# PixiFlood.net
KiCad netlist of a schematic drawn in EAGLE
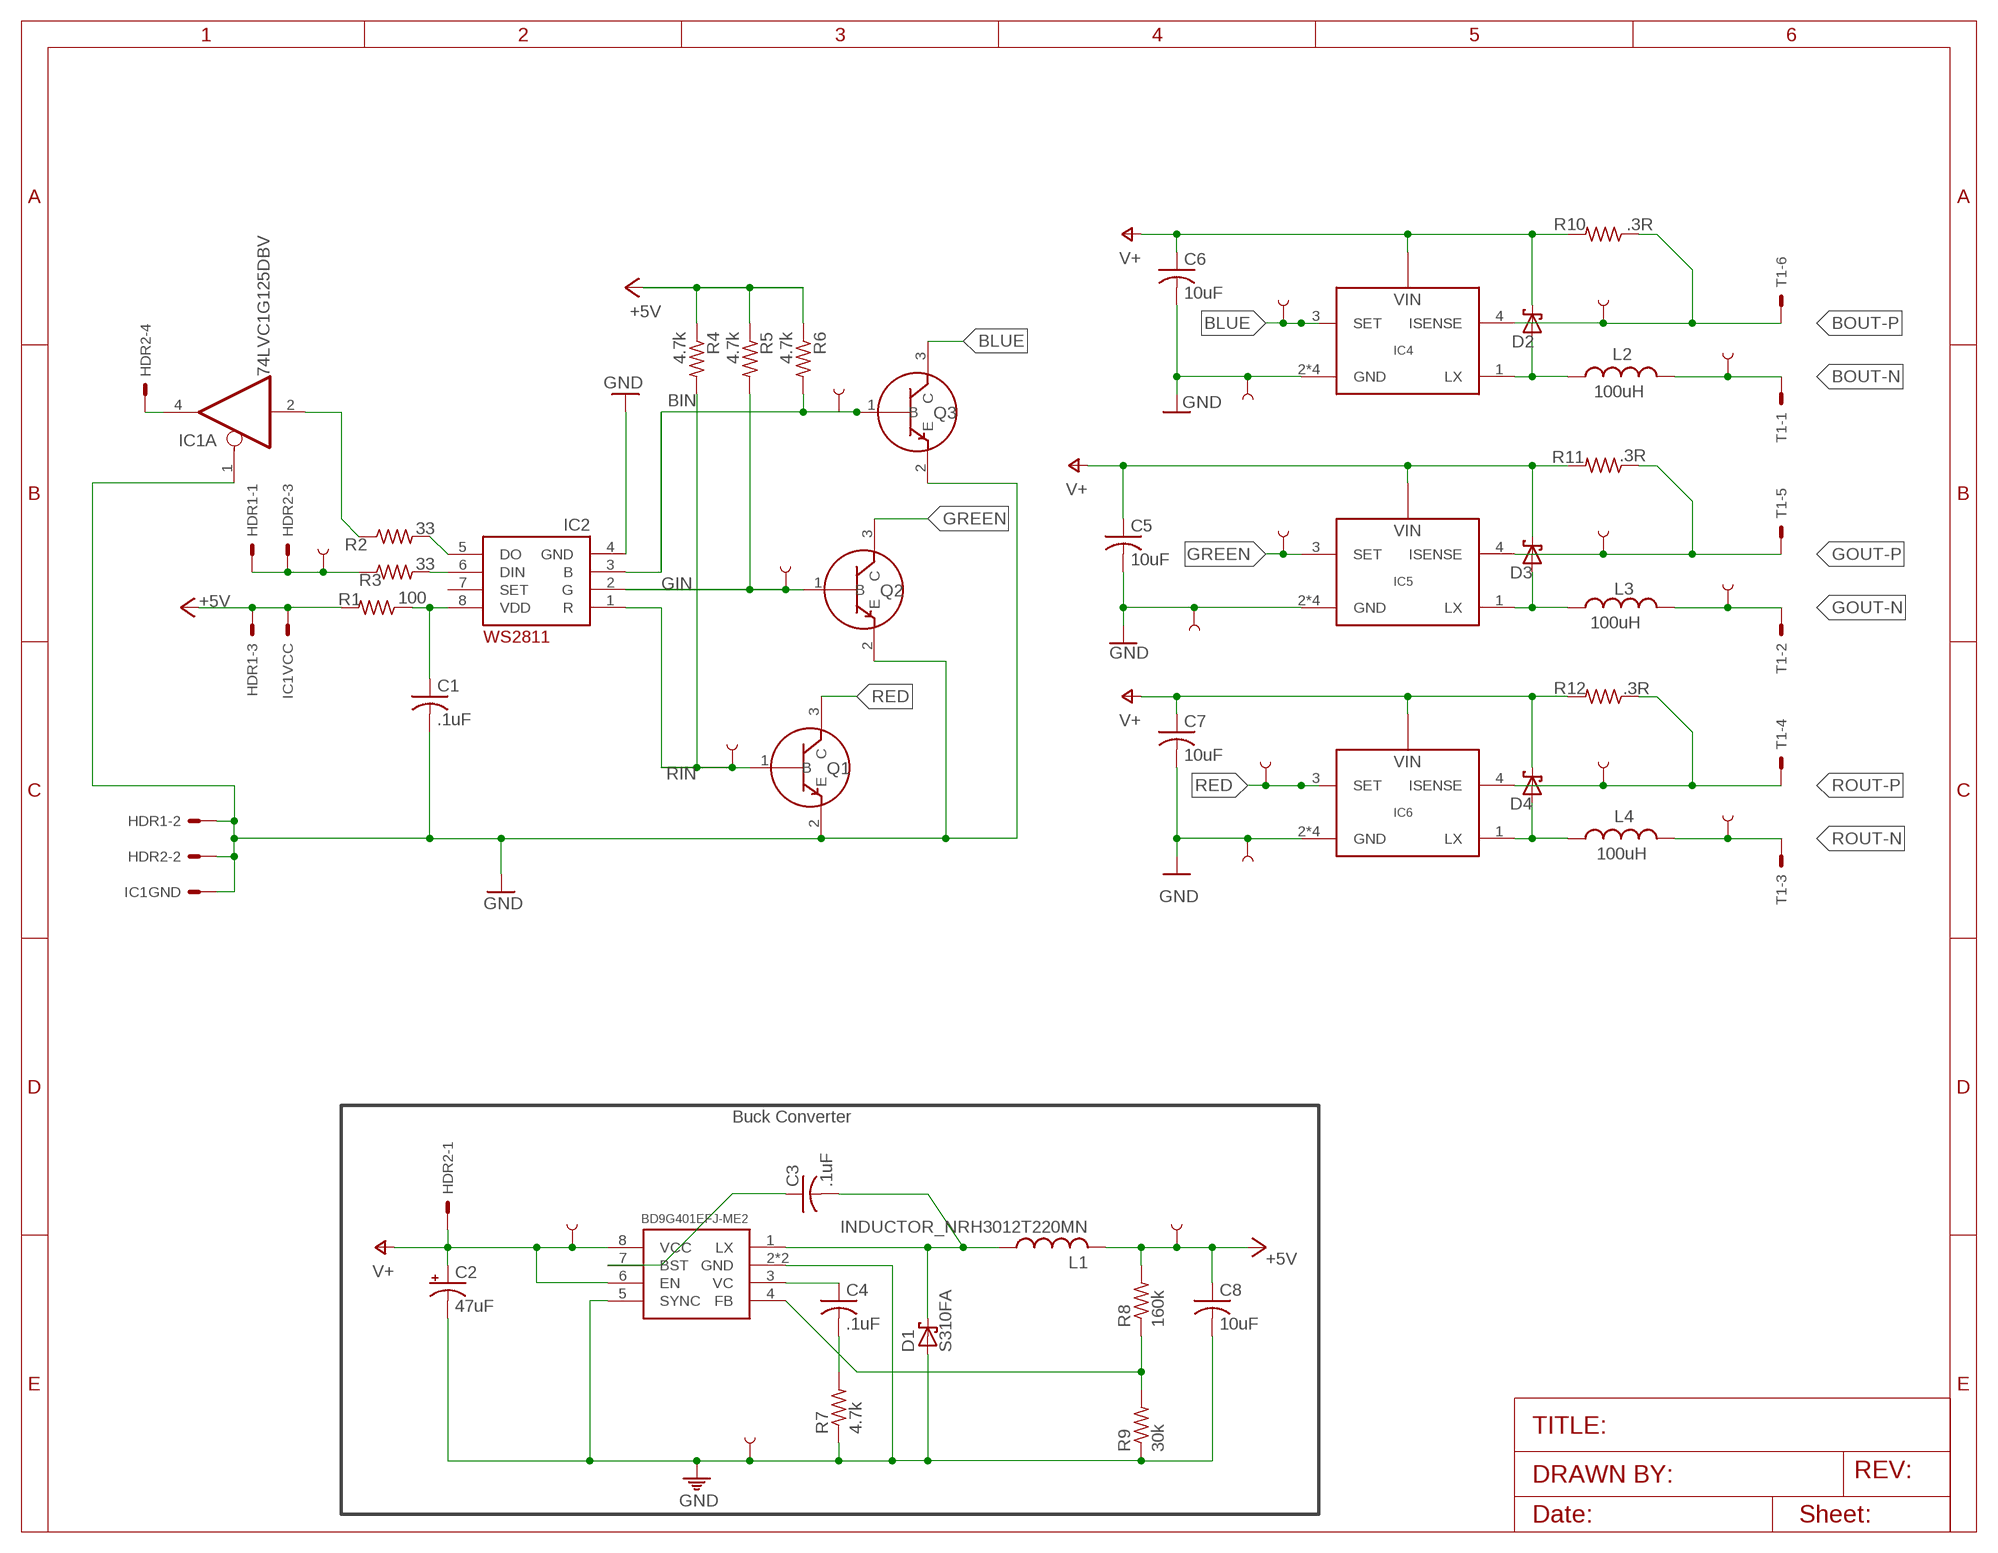
[diagram p0: schematic, sheet 1]

(export (version "E")
  (design (tool "Eeschema 10.0.6"))
  (components
    (comp (ref "C1")
      (value ".1uF")
      (footprint "eagle-import:C0805")
      (libsource (lib "eagle-import") (part "C-USC0805"))
    )
    (comp (ref "C2")
      (value "47uF")
      (footprint "eagle-import:UD-6,3X7,7_NICHICON")
      (libsource (lib "eagle-import") (part "CPOL-USUD-6,3X7,7"))
    )
    (comp (ref "C3")
      (value ".1uF")
      (footprint "eagle-import:C0805")
      (libsource (lib "eagle-import") (part "C-USC0805"))
    )
    (comp (ref "C4")
      (value ".1uF")
      (footprint "eagle-import:C0805")
      (libsource (lib "eagle-import") (part "C-USC0805"))
    )
    (comp (ref "C5")
      (value "10uF")
      (footprint "eagle-import:C1206")
      (libsource (lib "eagle-import") (part "C-USC1206"))
    )
    (comp (ref "C6")
      (value "10uF")
      (footprint "eagle-import:C1206")
      (libsource (lib "eagle-import") (part "C-USC1206"))
    )
    (comp (ref "C7")
      (value "10uF")
      (footprint "eagle-import:C1206")
      (libsource (lib "eagle-import") (part "C-USC1206"))
    )
    (comp (ref "C8")
      (value "10uF")
      (footprint "eagle-import:C1206")
      (libsource (lib "eagle-import") (part "C-USC1206"))
    )
    (comp (ref "D1")
      (value "S310FA")
      (footprint "eagle-import:SOD-123FL")
      (libsource (lib "eagle-import") (part "SCHOTTKY-DIODES310FA"))
    )
    (comp (ref "D2")
      (value "S310FA")
      (footprint "eagle-import:SOD-123FL")
      (libsource (lib "eagle-import") (part "SCHOTTKY-DIODES310FA"))
    )
    (comp (ref "D3")
      (value "S310FA")
      (footprint "eagle-import:SOD-123FL")
      (libsource (lib "eagle-import") (part "SCHOTTKY-DIODES310FA"))
    )
    (comp (ref "D4")
      (value "S310FA")
      (footprint "eagle-import:SOD-123FL")
      (libsource (lib "eagle-import") (part "SCHOTTKY-DIODES310FA"))
    )
    (comp (ref "HDR1")
      (value "M03FEMALE")
      (footprint "eagle-import:1X03_FEMALE")
      (libsource (lib "eagle-import") (part "M03FEMALE"))
    )
    (comp (ref "HDR2")
      (value "M04STD")
      (footprint "eagle-import:1X04")
      (libsource (lib "eagle-import") (part "M04STD"))
    )
    (comp (ref "IC1")
      (value "74LVC1G125DBV")
      (footprint "eagle-import:SOT23-5")
      (libsource (lib "eagle-import") (part "741G125DBVLVC"))
    )
    (comp (ref "IC2")
      (value "WS2811SOP8")
      (footprint "eagle-import:SO08-P-1.27")
      (libsource (lib "eagle-import") (part "WS2811SOP8"))
    )
    (comp (ref "IC3")
      (value "BD9G401EFJ-ME2")
      (footprint "eagle-import:SOIC127P600X100-9N")
      (libsource (lib "eagle-import") (part "BD9G401EFJ-ME2"))
    )
    (comp (ref "IC4")
      (value "AL-8861SOT89-5")
      (footprint "eagle-import:SOT89-5")
      (libsource (lib "eagle-import") (part "AL-8861SOT89-5"))
    )
    (comp (ref "IC5")
      (value "AL-8861SOT89-5")
      (footprint "eagle-import:SOT89-5")
      (libsource (lib "eagle-import") (part "AL-8861SOT89-5"))
    )
    (comp (ref "IC6")
      (value "AL-8861SOT89-5")
      (footprint "eagle-import:SOT89-5")
      (libsource (lib "eagle-import") (part "AL-8861SOT89-5"))
    )
    (comp (ref "L1")
      (value "INDUCTOR_NRH3012T220MN")
      (footprint "eagle-import:IND_TAIYO_NRH3012")
      (libsource (lib "eagle-import") (part "INDUCTOR_NRH3012T220MN"))
    )
    (comp (ref "L2")
      (value "100uH")
      (footprint "eagle-import:SLF7045")
      (libsource (lib "eagle-import") (part "INDUCTOR_TDK"))
    )
    (comp (ref "L3")
      (value "100uH")
      (footprint "eagle-import:SLF7045")
      (libsource (lib "eagle-import") (part "INDUCTOR_TDK"))
    )
    (comp (ref "L4")
      (value "100uH")
      (footprint "eagle-import:SLF7045")
      (libsource (lib "eagle-import") (part "INDUCTOR_TDK"))
    )
    (comp (ref "Q1")
      (value "BC847BC847")
      (footprint "eagle-import:SOT23-3")
      (libsource (lib "eagle-import") (part "BC847BC847"))
    )
    (comp (ref "Q2")
      (value "BC847BC847")
      (footprint "eagle-import:SOT23-3")
      (libsource (lib "eagle-import") (part "BC847BC847"))
    )
    (comp (ref "Q3")
      (value "BC847BC847")
      (footprint "eagle-import:SOT23-3")
      (libsource (lib "eagle-import") (part "BC847BC847"))
    )
    (comp (ref "R1")
      (value "100")
      (footprint "eagle-import:R0805")
      (libsource (lib "eagle-import") (part "R-US_R0805"))
    )
    (comp (ref "R2")
      (value "33")
      (footprint "eagle-import:R0805")
      (libsource (lib "eagle-import") (part "R-US_R0805"))
    )
    (comp (ref "R3")
      (value "33")
      (footprint "eagle-import:R0805")
      (libsource (lib "eagle-import") (part "R-US_R0805"))
    )
    (comp (ref "R4")
      (value "4.7k")
      (footprint "eagle-import:R0805")
      (libsource (lib "eagle-import") (part "R-US_R0805"))
    )
    (comp (ref "R5")
      (value "4.7k")
      (footprint "eagle-import:R0805")
      (libsource (lib "eagle-import") (part "R-US_R0805"))
    )
    (comp (ref "R6")
      (value "4.7k")
      (footprint "eagle-import:R0805")
      (libsource (lib "eagle-import") (part "R-US_R0805"))
    )
    (comp (ref "R7")
      (value "4.7k")
      (footprint "eagle-import:R0805")
      (libsource (lib "eagle-import") (part "R-US_R0805"))
    )
    (comp (ref "R8")
      (value "160k")
      (footprint "eagle-import:R0805")
      (libsource (lib "eagle-import") (part "R-US_R0805"))
    )
    (comp (ref "R9")
      (value "30k")
      (footprint "eagle-import:R0805")
      (libsource (lib "eagle-import") (part "R-US_R0805"))
    )
    (comp (ref "R10")
      (value ".3R")
      (footprint "eagle-import:R1210")
      (libsource (lib "eagle-import") (part "R-US_R1210"))
    )
    (comp (ref "R11")
      (value ".3R")
      (footprint "eagle-import:R1210")
      (libsource (lib "eagle-import") (part "R-US_R1210"))
    )
    (comp (ref "R12")
      (value ".3R")
      (footprint "eagle-import:R1210")
      (libsource (lib "eagle-import") (part "R-US_R1210"))
    )
    (comp (ref "T1")
      (value "M06SIP")
      (footprint "eagle-import:1X06")
      (libsource (lib "eagle-import") (part "M06SIP"))
    )
    (comp (ref "TP1")
      (value "ROUT-N")
      (footprint "eagle-import:TP-1")
      (libsource (lib "eagle-import") (part "TEST_PINTP-1"))
    )
    (comp (ref "TP2")
      (value "GOUT-N")
      (footprint "eagle-import:TP-1")
      (libsource (lib "eagle-import") (part "TEST_PINTP-1"))
    )
    (comp (ref "TP3")
      (value "BOUT-N")
      (footprint "eagle-import:TP-1")
      (libsource (lib "eagle-import") (part "TEST_PINTP-1"))
    )
    (comp (ref "TP4")
      (value "RED")
      (footprint "eagle-import:TP-1")
      (libsource (lib "eagle-import") (part "TEST_PINTP-1"))
    )
    (comp (ref "TP5")
      (value "BLUE")
      (footprint "eagle-import:TP-1")
      (libsource (lib "eagle-import") (part "TEST_PINTP-1"))
    )
    (comp (ref "TP6")
      (value "GREEN")
      (footprint "eagle-import:TP-1")
      (libsource (lib "eagle-import") (part "TEST_PINTP-1"))
    )
    (comp (ref "TP7")
      (value "BOUT-P")
      (footprint "eagle-import:TP-1")
      (libsource (lib "eagle-import") (part "TEST_PINTP-1"))
    )
    (comp (ref "TP8")
      (value "GOUT-P")
      (footprint "eagle-import:TP-1")
      (libsource (lib "eagle-import") (part "TEST_PINTP-1"))
    )
    (comp (ref "TP9")
      (value "ROUT-R")
      (footprint "eagle-import:TP-1")
      (libsource (lib "eagle-import") (part "TEST_PINTP-1"))
    )
    (comp (ref "TP11")
      (value "RIN")
      (footprint "eagle-import:TP-1")
      (libsource (lib "eagle-import") (part "TEST_PINTP-1"))
    )
    (comp (ref "TP12")
      (value "VIN")
      (footprint "eagle-import:TP-1")
      (libsource (lib "eagle-import") (part "TEST_PINTP-1"))
    )
    (comp (ref "TP13")
      (value "DIN")
      (footprint "eagle-import:TP-1")
      (libsource (lib "eagle-import") (part "TEST_PINTP-1"))
    )
    (comp (ref "TP14")
      (value "GND")
      (footprint "eagle-import:TP-1")
      (libsource (lib "eagle-import") (part "TEST_PINTP-1"))
    )
    (comp (ref "TP15")
      (value "5V")
      (footprint "eagle-import:TP-1")
      (libsource (lib "eagle-import") (part "TEST_PINTP-1"))
    )
    (comp (ref "TP19")
      (value "GND")
      (footprint "eagle-import:TP-1")
      (libsource (lib "eagle-import") (part "TEST_PINTP-1"))
    )
    (comp (ref "TP20")
      (value "GND")
      (footprint "eagle-import:TP-1")
      (libsource (lib "eagle-import") (part "TEST_PINTP-1"))
    )
    (comp (ref "TP21")
      (value "BIN")
      (footprint "eagle-import:TP-1")
      (libsource (lib "eagle-import") (part "TEST_PINTP-1"))
    )
    (comp (ref "TP22")
      (value "GIN")
      (footprint "eagle-import:TP-1")
      (libsource (lib "eagle-import") (part "TEST_PINTP-1"))
    )
    (comp (ref "TP23")
      (value "GND")
      (footprint "eagle-import:TP-1")
      (libsource (lib "eagle-import") (part "TEST_PINTP-1"))
    )
  )
  (nets
    (net (code "1") (name "+5V") (class "Default")
      (node (ref "C8") (pin "1") (pinfunction "1_1") (pintype "passive"))
      (node (ref "HDR1") (pin "5") (pinfunction "S_5") (pintype "passive"))
      (node (ref "IC1") (pin "5") (pinfunction "S_5") (pintype "passive"))
      (node (ref "L1") (pin "2") (pinfunction "2_2") (pintype "passive"))
      (node (ref "R1") (pin "2") (pinfunction "2_2") (pintype "passive"))
      (node (ref "R4") (pin "1") (pinfunction "1_1") (pintype "passive"))
      (node (ref "R5") (pin "1") (pinfunction "1_1") (pintype "passive"))
      (node (ref "R6") (pin "1") (pinfunction "1_1") (pintype "passive"))
      (node (ref "R8") (pin "2") (pinfunction "2_2") (pintype "passive"))
      (node (ref "TP15") (pin "P$1") (pinfunction "1_P$1") (pintype "bidirectional"))
    )
    (net (code "2") (name "/BIN") (class "Default")
      (node (ref "IC2") (pin "3") (pinfunction "B_3") (pintype "open_collector"))
      (node (ref "Q3") (pin "1") (pinfunction "B_1") (pintype "bidirectional"))
      (node (ref "R6") (pin "2") (pinfunction "2_2") (pintype "passive"))
      (node (ref "TP21") (pin "P$1") (pinfunction "1_P$1") (pintype "bidirectional"))
    )
    (net (code "3") (name "/GIN") (class "Default")
      (node (ref "IC2") (pin "2") (pinfunction "G_2") (pintype "open_collector"))
      (node (ref "Q2") (pin "1") (pinfunction "B_1") (pintype "bidirectional"))
      (node (ref "R5") (pin "2") (pinfunction "2_2") (pintype "passive"))
      (node (ref "TP22") (pin "P$1") (pinfunction "1_P$1") (pintype "bidirectional"))
    )
    (net (code "4") (name "/RIN") (class "Default")
      (node (ref "IC2") (pin "1") (pinfunction "R_1") (pintype "open_collector"))
      (node (ref "Q1") (pin "1") (pinfunction "B_1") (pintype "bidirectional"))
      (node (ref "R4") (pin "2") (pinfunction "2_2") (pintype "passive"))
      (node (ref "TP11") (pin "P$1") (pinfunction "1_P$1") (pintype "bidirectional"))
    )
    (net (code "5") (name "BLUE") (class "Default")
      (node (ref "IC4") (pin "3") (pinfunction "SET_3") (pintype "bidirectional"))
      (node (ref "Q3") (pin "3") (pinfunction "C_3") (pintype "bidirectional"))
      (node (ref "TP5") (pin "P$1") (pinfunction "1_P$1") (pintype "bidirectional"))
    )
    (net (code "6") (name "BOUT-N") (class "Default")
      (node (ref "L2") (pin "2") (pinfunction "2_2") (pintype "passive"))
      (node (ref "T1") (pin "1") (pinfunction "S_1") (pintype "passive"))
      (node (ref "TP3") (pin "P$1") (pinfunction "1_P$1") (pintype "bidirectional"))
    )
    (net (code "7") (name "BOUT-P") (class "Default")
      (node (ref "IC4") (pin "4") (pinfunction "ISENSE_4") (pintype "bidirectional"))
      (node (ref "R10") (pin "1") (pinfunction "1_1") (pintype "passive"))
      (node (ref "T1") (pin "6") (pinfunction "S_6") (pintype "passive"))
      (node (ref "TP7") (pin "P$1") (pinfunction "1_P$1") (pintype "bidirectional"))
    )
    (net (code "8") (name "GND") (class "Default")
      (node (ref "C1") (pin "2") (pinfunction "2_2") (pintype "passive"))
      (node (ref "C2") (pin "-") (pinfunction "-_-") (pintype "passive"))
      (node (ref "C5") (pin "2") (pinfunction "2_2") (pintype "passive"))
      (node (ref "C6") (pin "2") (pinfunction "2_2") (pintype "passive"))
      (node (ref "C7") (pin "2") (pinfunction "2_2") (pintype "passive"))
      (node (ref "C8") (pin "2") (pinfunction "2_2") (pintype "passive"))
      (node (ref "D1") (pin "A") (pinfunction "A_A") (pintype "passive"))
      (node (ref "HDR1") (pin "3") (pinfunction "S_3") (pintype "passive"))
      (node (ref "HDR2") (pin "2") (pinfunction "S_2") (pintype "passive"))
      (node (ref "IC1") (pin "1") (pinfunction "OE_1") (pintype "input"))
      (node (ref "IC1") (pin "3") (pinfunction "S_3") (pintype "passive"))
      (node (ref "IC2") (pin "4") (pinfunction "GND_4") (pintype "power_in"))
      (node (ref "IC3") (pin "2") (pinfunction "GND_2") (pintype "power_in"))
      (node (ref "IC3") (pin "5") (pinfunction "SYNC_5") (pintype "bidirectional"))
      (node (ref "IC3") (pin "9") (pinfunction "GND_9") (pintype "power_in"))
      (node (ref "IC4") (pin "2") (pinfunction "GND_2") (pintype "power_in"))
      (node (ref "IC4") (pin "2@1") (pinfunction "GND_2@1") (pintype "power_in"))
      (node (ref "IC4") (pin "2@2") (pinfunction "GND_2@2") (pintype "power_in"))
      (node (ref "IC4") (pin "2@3") (pinfunction "GND_2@3") (pintype "power_in"))
      (node (ref "IC5") (pin "2") (pinfunction "GND_2") (pintype "power_in"))
      (node (ref "IC5") (pin "2@1") (pinfunction "GND_2@1") (pintype "power_in"))
      (node (ref "IC5") (pin "2@2") (pinfunction "GND_2@2") (pintype "power_in"))
      (node (ref "IC5") (pin "2@3") (pinfunction "GND_2@3") (pintype "power_in"))
      (node (ref "IC6") (pin "2") (pinfunction "GND_2") (pintype "power_in"))
      (node (ref "IC6") (pin "2@1") (pinfunction "GND_2@1") (pintype "power_in"))
      (node (ref "IC6") (pin "2@2") (pinfunction "GND_2@2") (pintype "power_in"))
      (node (ref "IC6") (pin "2@3") (pinfunction "GND_2@3") (pintype "power_in"))
      (node (ref "Q1") (pin "2") (pinfunction "E_2") (pintype "bidirectional"))
      (node (ref "Q2") (pin "2") (pinfunction "E_2") (pintype "bidirectional"))
      (node (ref "Q3") (pin "2") (pinfunction "E_2") (pintype "bidirectional"))
      (node (ref "R7") (pin "1") (pinfunction "1_1") (pintype "passive"))
      (node (ref "R9") (pin "1") (pinfunction "1_1") (pintype "passive"))
      (node (ref "TP14") (pin "P$1") (pinfunction "1_P$1") (pintype "bidirectional"))
      (node (ref "TP19") (pin "P$1") (pinfunction "1_P$1") (pintype "bidirectional"))
      (node (ref "TP20") (pin "P$1") (pinfunction "1_P$1") (pintype "bidirectional"))
      (node (ref "TP23") (pin "P$1") (pinfunction "1_P$1") (pintype "bidirectional"))
    )
    (net (code "9") (name "GOUT-N") (class "Default")
      (node (ref "L3") (pin "2") (pinfunction "2_2") (pintype "passive"))
      (node (ref "T1") (pin "2") (pinfunction "S_2") (pintype "passive"))
      (node (ref "TP2") (pin "P$1") (pinfunction "1_P$1") (pintype "bidirectional"))
    )
    (net (code "10") (name "GOUT-P") (class "Default")
      (node (ref "IC5") (pin "4") (pinfunction "ISENSE_4") (pintype "bidirectional"))
      (node (ref "R11") (pin "1") (pinfunction "1_1") (pintype "passive"))
      (node (ref "T1") (pin "5") (pinfunction "S_5") (pintype "passive"))
      (node (ref "TP8") (pin "P$1") (pinfunction "1_P$1") (pintype "bidirectional"))
    )
    (net (code "11") (name "GREEN") (class "Default")
      (node (ref "IC5") (pin "3") (pinfunction "SET_3") (pintype "bidirectional"))
      (node (ref "Q2") (pin "3") (pinfunction "C_3") (pintype "bidirectional"))
      (node (ref "TP6") (pin "P$1") (pinfunction "1_P$1") (pintype "bidirectional"))
    )
    (net (code "12") (name "Net-(C4-Pad2)") (class "Default")
      (node (ref "C4") (pin "2") (pinfunction "2_2") (pintype "passive"))
      (node (ref "R7") (pin "2") (pinfunction "2_2") (pintype "passive"))
    )
    (net (code "13") (name "Net-(HDR1A-S)") (class "Default")
      (node (ref "HDR1") (pin "1") (pinfunction "S_1") (pintype "passive"))
      (node (ref "HDR2") (pin "3") (pinfunction "S_3") (pintype "passive"))
      (node (ref "R3") (pin "1") (pinfunction "1_1") (pintype "passive"))
      (node (ref "TP13") (pin "P$1") (pinfunction "1_P$1") (pintype "bidirectional"))
    )
    (net (code "14") (name "Net-(HDR2D-S)") (class "Default")
      (node (ref "HDR2") (pin "4") (pinfunction "S_4") (pintype "passive"))
      (node (ref "IC1") (pin "4") (pinfunction "O_4") (pintype "tri_state"))
    )
    (net (code "15") (name "Net-(IC1A-I)") (class "Default")
      (node (ref "IC1") (pin "2") (pinfunction "I_2") (pintype "input"))
      (node (ref "R2") (pin "1") (pinfunction "1_1") (pintype "passive"))
    )
    (net (code "16") (name "Net-(IC2-DIN)") (class "Default")
      (node (ref "IC2") (pin "6") (pinfunction "DIN_6") (pintype "input"))
      (node (ref "R3") (pin "2") (pinfunction "2_2") (pintype "passive"))
    )
    (net (code "17") (name "Net-(IC2-DO)") (class "Default")
      (node (ref "IC2") (pin "5") (pinfunction "DO_5") (pintype "output"))
      (node (ref "R2") (pin "2") (pinfunction "2_2") (pintype "passive"))
    )
    (net (code "18") (name "Net-(IC2-VDD)") (class "Default")
      (node (ref "C1") (pin "1") (pinfunction "1_1") (pintype "passive"))
      (node (ref "IC2") (pin "8") (pinfunction "VDD_8") (pintype "power_in"))
      (node (ref "R1") (pin "1") (pinfunction "1_1") (pintype "passive"))
    )
    (net (code "19") (name "Net-(IC3-BST)") (class "Default")
      (node (ref "C3") (pin "1") (pinfunction "1_1") (pintype "passive"))
      (node (ref "IC3") (pin "7") (pinfunction "BST_7") (pintype "bidirectional"))
    )
    (net (code "20") (name "Net-(IC3-FB)") (class "Default")
      (node (ref "IC3") (pin "4") (pinfunction "FB_4") (pintype "bidirectional"))
      (node (ref "R8") (pin "1") (pinfunction "1_1") (pintype "passive"))
      (node (ref "R9") (pin "2") (pinfunction "2_2") (pintype "passive"))
    )
    (net (code "21") (name "Net-(IC3-LX)") (class "Default")
      (node (ref "C3") (pin "2") (pinfunction "2_2") (pintype "passive"))
      (node (ref "D1") (pin "C") (pinfunction "C_C") (pintype "passive"))
      (node (ref "IC3") (pin "1") (pinfunction "LX_1") (pintype "bidirectional"))
      (node (ref "L1") (pin "1") (pinfunction "1_1") (pintype "passive"))
    )
    (net (code "22") (name "Net-(IC3-VC)") (class "Default")
      (node (ref "C4") (pin "1") (pinfunction "1_1") (pintype "passive"))
      (node (ref "IC3") (pin "3") (pinfunction "VC_3") (pintype "bidirectional"))
    )
    (net (code "23") (name "Net-(IC4-LX)") (class "Default")
      (node (ref "D2") (pin "A") (pinfunction "A_A") (pintype "passive"))
      (node (ref "IC4") (pin "1") (pinfunction "LX_1") (pintype "bidirectional"))
      (node (ref "L2") (pin "1") (pinfunction "1_1") (pintype "passive"))
    )
    (net (code "24") (name "Net-(IC5-LX)") (class "Default")
      (node (ref "D3") (pin "A") (pinfunction "A_A") (pintype "passive"))
      (node (ref "IC5") (pin "1") (pinfunction "LX_1") (pintype "bidirectional"))
      (node (ref "L3") (pin "1") (pinfunction "1_1") (pintype "passive"))
    )
    (net (code "25") (name "Net-(IC6-LX)") (class "Default")
      (node (ref "D4") (pin "A") (pinfunction "A_A") (pintype "passive"))
      (node (ref "IC6") (pin "1") (pinfunction "LX_1") (pintype "bidirectional"))
      (node (ref "L4") (pin "1") (pinfunction "1_1") (pintype "passive"))
    )
    (net (code "26") (name "RED") (class "Default")
      (node (ref "IC6") (pin "3") (pinfunction "SET_3") (pintype "bidirectional"))
      (node (ref "Q1") (pin "3") (pinfunction "C_3") (pintype "bidirectional"))
      (node (ref "TP4") (pin "P$1") (pinfunction "1_P$1") (pintype "bidirectional"))
    )
    (net (code "27") (name "ROUT-N") (class "Default")
      (node (ref "L4") (pin "2") (pinfunction "2_2") (pintype "passive"))
      (node (ref "T1") (pin "3") (pinfunction "S_3") (pintype "passive"))
      (node (ref "TP1") (pin "P$1") (pinfunction "1_P$1") (pintype "bidirectional"))
    )
    (net (code "28") (name "ROUT-P") (class "Default")
      (node (ref "IC6") (pin "4") (pinfunction "ISENSE_4") (pintype "bidirectional"))
      (node (ref "R12") (pin "1") (pinfunction "1_1") (pintype "passive"))
      (node (ref "T1") (pin "4") (pinfunction "S_4") (pintype "passive"))
      (node (ref "TP9") (pin "P$1") (pinfunction "1_P$1") (pintype "bidirectional"))
    )
    (net (code "29") (name "V+") (class "Default")
      (node (ref "C2") (pin "+") (pinfunction "+_+") (pintype "passive"))
      (node (ref "C5") (pin "1") (pinfunction "1_1") (pintype "passive"))
      (node (ref "C6") (pin "1") (pinfunction "1_1") (pintype "passive"))
      (node (ref "C7") (pin "1") (pinfunction "1_1") (pintype "passive"))
      (node (ref "D2") (pin "C") (pinfunction "C_C") (pintype "passive"))
      (node (ref "D3") (pin "C") (pinfunction "C_C") (pintype "passive"))
      (node (ref "D4") (pin "C") (pinfunction "C_C") (pintype "passive"))
      (node (ref "HDR2") (pin "1") (pinfunction "S_1") (pintype "passive"))
      (node (ref "IC3") (pin "6") (pinfunction "EN_6") (pintype "bidirectional"))
      (node (ref "IC3") (pin "8") (pinfunction "VCC_8") (pintype "power_in"))
      (node (ref "IC4") (pin "5") (pinfunction "VIN_5") (pintype "power_in"))
      (node (ref "IC5") (pin "5") (pinfunction "VIN_5") (pintype "power_in"))
      (node (ref "IC6") (pin "5") (pinfunction "VIN_5") (pintype "power_in"))
      (node (ref "R10") (pin "2") (pinfunction "2_2") (pintype "passive"))
      (node (ref "R11") (pin "2") (pinfunction "2_2") (pintype "passive"))
      (node (ref "R12") (pin "2") (pinfunction "2_2") (pintype "passive"))
      (node (ref "TP12") (pin "P$1") (pinfunction "1_P$1") (pintype "bidirectional"))
    )
    (net (code "30") (name "unconnected-(IC2-SET-Pad7)") (class "Default")
      (node (ref "IC2") (pin "7") (pinfunction "SET_7") (pintype "input"))
    )
  )
)
